# hmc_power.net
KiCad netlist of a schematic drawn in EAGLE
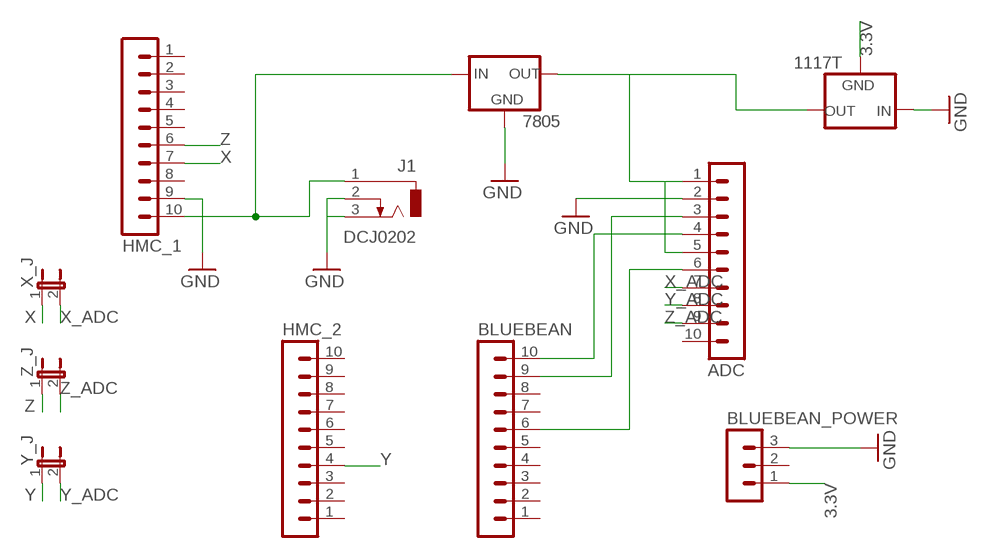
[diagram p0: schematic, sheet 1]

(export (version "E")
  (design (tool "Eeschema 10.0.6"))
  (components
    (comp (ref "1117T")
      (value "78XXL")
      (footprint "eagle-import:78XXL")
      (libsource (lib "eagle-import") (part "78XXL"))
    )
    (comp (ref "7805")
      (value "78XXL")
      (footprint "eagle-import:78XXL")
      (libsource (lib "eagle-import") (part "78XXL"))
    )
    (comp (ref "ADC")
      (value "MA10-1")
      (footprint "eagle-import:MA10-1")
      (libsource (lib "eagle-import") (part "MA10-1"))
    )
    (comp (ref "BLUEBEAN")
      (value "MA10-1")
      (footprint "eagle-import:MA10-1")
      (libsource (lib "eagle-import") (part "MA10-1"))
    )
    (comp (ref "BLUEBEAN_POWER")
      (value "MA03-1")
      (footprint "eagle-import:MA03-1")
      (libsource (lib "eagle-import") (part "MA03-1"))
    )
    (comp (ref "HMC_1")
      (value "MA10-1")
      (footprint "eagle-import:MA10-1")
      (libsource (lib "eagle-import") (part "MA10-1"))
    )
    (comp (ref "HMC_2")
      (value "MA10-1")
      (footprint "eagle-import:MA10-1")
      (libsource (lib "eagle-import") (part "MA10-1"))
    )
    (comp (ref "J1")
      (value "DCJ0202")
      (footprint "eagle-import:DCJ0202")
      (libsource (lib "eagle-import") (part "DCJ0202"))
    )
    (comp (ref "X_J")
      (value "JP1E")
      (footprint "eagle-import:JP1")
      (libsource (lib "eagle-import") (part "JP1E"))
    )
    (comp (ref "Y_J")
      (value "JP1E")
      (footprint "eagle-import:JP1")
      (libsource (lib "eagle-import") (part "JP1E"))
    )
    (comp (ref "Z_J")
      (value "JP1E")
      (footprint "eagle-import:JP1")
      (libsource (lib "eagle-import") (part "JP1E"))
    )
  )
  (nets
    (net (code "1") (name "/3.3V") (class "Default")
      (node (ref "1117T") (pin "GND") (pinfunction "GND_GND") (pintype "input"))
      (node (ref "BLUEBEAN_POWER") (pin "1") (pinfunction "1_1") (pintype "passive"))
    )
    (net (code "2") (name "/X") (class "Default")
      (node (ref "HMC_1") (pin "7") (pinfunction "7_7") (pintype "passive"))
      (node (ref "X_J") (pin "1") (pinfunction "1_1") (pintype "passive"))
    )
    (net (code "3") (name "/X_ADC") (class "Default")
      (node (ref "ADC") (pin "7") (pinfunction "7_7") (pintype "passive"))
      (node (ref "X_J") (pin "2") (pinfunction "2_2") (pintype "passive"))
    )
    (net (code "4") (name "/Y") (class "Default")
      (node (ref "HMC_2") (pin "4") (pinfunction "4_4") (pintype "passive"))
      (node (ref "Y_J") (pin "1") (pinfunction "1_1") (pintype "passive"))
    )
    (net (code "5") (name "/Y_ADC") (class "Default")
      (node (ref "ADC") (pin "8") (pinfunction "8_8") (pintype "passive"))
      (node (ref "Y_J") (pin "2") (pinfunction "2_2") (pintype "passive"))
    )
    (net (code "6") (name "/Z") (class "Default")
      (node (ref "HMC_1") (pin "6") (pinfunction "6_6") (pintype "passive"))
      (node (ref "Z_J") (pin "1") (pinfunction "1_1") (pintype "passive"))
    )
    (net (code "7") (name "/Z_ADC") (class "Default")
      (node (ref "ADC") (pin "9") (pinfunction "9_9") (pintype "passive"))
      (node (ref "Z_J") (pin "2") (pinfunction "2_2") (pintype "passive"))
    )
    (net (code "8") (name "GND") (class "Default")
      (node (ref "1117T") (pin "IN") (pinfunction "IN_IN") (pintype "input"))
      (node (ref "7805") (pin "GND") (pinfunction "GND_GND") (pintype "input"))
      (node (ref "ADC") (pin "2") (pinfunction "2_2") (pintype "passive"))
      (node (ref "BLUEBEAN_POWER") (pin "3") (pinfunction "3_3") (pintype "passive"))
      (node (ref "HMC_1") (pin "9") (pinfunction "9_9") (pintype "passive"))
      (node (ref "J1") (pin "2") (pinfunction "2_2") (pintype "passive"))
      (node (ref "J1") (pin "3") (pinfunction "3_3") (pintype "passive"))
    )
    (net (code "9") (name "Net-(1117T-PadOUT)") (class "Default")
      (node (ref "1117T") (pin "OUT") (pinfunction "OUT_OUT") (pintype "passive"))
      (node (ref "7805") (pin "OUT") (pinfunction "OUT_OUT") (pintype "passive"))
      (node (ref "ADC") (pin "1") (pinfunction "1_1") (pintype "passive"))
      (node (ref "ADC") (pin "5") (pinfunction "5_5") (pintype "passive"))
    )
    (net (code "10") (name "Net-(7805-PadIN)") (class "Default")
      (node (ref "7805") (pin "IN") (pinfunction "IN_IN") (pintype "input"))
      (node (ref "HMC_1") (pin "10") (pinfunction "10_10") (pintype "passive"))
      (node (ref "J1") (pin "1") (pinfunction "1_1") (pintype "passive"))
    )
    (net (code "11") (name "Net-(ADC-Pad3)") (class "Default")
      (node (ref "ADC") (pin "3") (pinfunction "3_3") (pintype "passive"))
      (node (ref "BLUEBEAN") (pin "9") (pinfunction "9_9") (pintype "passive"))
    )
    (net (code "12") (name "Net-(ADC-Pad4)") (class "Default")
      (node (ref "ADC") (pin "4") (pinfunction "4_4") (pintype "passive"))
      (node (ref "BLUEBEAN") (pin "10") (pinfunction "10_10") (pintype "passive"))
    )
    (net (code "13") (name "Net-(ADC-Pad6)") (class "Default")
      (node (ref "ADC") (pin "6") (pinfunction "6_6") (pintype "passive"))
      (node (ref "BLUEBEAN") (pin "6") (pinfunction "6_6") (pintype "passive"))
    )
    (net (code "14") (name "unconnected-(ADC-Pad10)") (class "Default")
      (node (ref "ADC") (pin "10") (pinfunction "10_10") (pintype "passive"))
    )
    (net (code "15") (name "unconnected-(BLUEBEAN-Pad1)") (class "Default")
      (node (ref "BLUEBEAN") (pin "1") (pinfunction "1_1") (pintype "passive"))
    )
    (net (code "16") (name "unconnected-(BLUEBEAN-Pad2)") (class "Default")
      (node (ref "BLUEBEAN") (pin "2") (pinfunction "2_2") (pintype "passive"))
    )
    (net (code "17") (name "unconnected-(BLUEBEAN-Pad3)") (class "Default")
      (node (ref "BLUEBEAN") (pin "3") (pinfunction "3_3") (pintype "passive"))
    )
    (net (code "18") (name "unconnected-(BLUEBEAN-Pad4)") (class "Default")
      (node (ref "BLUEBEAN") (pin "4") (pinfunction "4_4") (pintype "passive"))
    )
    (net (code "19") (name "unconnected-(BLUEBEAN-Pad5)") (class "Default")
      (node (ref "BLUEBEAN") (pin "5") (pinfunction "5_5") (pintype "passive"))
    )
    (net (code "20") (name "unconnected-(BLUEBEAN-Pad7)") (class "Default")
      (node (ref "BLUEBEAN") (pin "7") (pinfunction "7_7") (pintype "passive"))
    )
    (net (code "21") (name "unconnected-(BLUEBEAN-Pad8)") (class "Default")
      (node (ref "BLUEBEAN") (pin "8") (pinfunction "8_8") (pintype "passive"))
    )
    (net (code "22") (name "unconnected-(BLUEBEAN_POWER-Pad2)") (class "Default")
      (node (ref "BLUEBEAN_POWER") (pin "2") (pinfunction "2_2") (pintype "passive"))
    )
    (net (code "23") (name "unconnected-(HMC_1-Pad1)") (class "Default")
      (node (ref "HMC_1") (pin "1") (pinfunction "1_1") (pintype "passive"))
    )
    (net (code "24") (name "unconnected-(HMC_1-Pad2)") (class "Default")
      (node (ref "HMC_1") (pin "2") (pinfunction "2_2") (pintype "passive"))
    )
    (net (code "25") (name "unconnected-(HMC_1-Pad3)") (class "Default")
      (node (ref "HMC_1") (pin "3") (pinfunction "3_3") (pintype "passive"))
    )
    (net (code "26") (name "unconnected-(HMC_1-Pad4)") (class "Default")
      (node (ref "HMC_1") (pin "4") (pinfunction "4_4") (pintype "passive"))
    )
    (net (code "27") (name "unconnected-(HMC_1-Pad5)") (class "Default")
      (node (ref "HMC_1") (pin "5") (pinfunction "5_5") (pintype "passive"))
    )
    (net (code "28") (name "unconnected-(HMC_1-Pad8)") (class "Default")
      (node (ref "HMC_1") (pin "8") (pinfunction "8_8") (pintype "passive"))
    )
    (net (code "29") (name "unconnected-(HMC_2-Pad1)") (class "Default")
      (node (ref "HMC_2") (pin "1") (pinfunction "1_1") (pintype "passive"))
    )
    (net (code "30") (name "unconnected-(HMC_2-Pad2)") (class "Default")
      (node (ref "HMC_2") (pin "2") (pinfunction "2_2") (pintype "passive"))
    )
    (net (code "31") (name "unconnected-(HMC_2-Pad3)") (class "Default")
      (node (ref "HMC_2") (pin "3") (pinfunction "3_3") (pintype "passive"))
    )
    (net (code "32") (name "unconnected-(HMC_2-Pad5)") (class "Default")
      (node (ref "HMC_2") (pin "5") (pinfunction "5_5") (pintype "passive"))
    )
    (net (code "33") (name "unconnected-(HMC_2-Pad6)") (class "Default")
      (node (ref "HMC_2") (pin "6") (pinfunction "6_6") (pintype "passive"))
    )
    (net (code "34") (name "unconnected-(HMC_2-Pad7)") (class "Default")
      (node (ref "HMC_2") (pin "7") (pinfunction "7_7") (pintype "passive"))
    )
    (net (code "35") (name "unconnected-(HMC_2-Pad8)") (class "Default")
      (node (ref "HMC_2") (pin "8") (pinfunction "8_8") (pintype "passive"))
    )
    (net (code "36") (name "unconnected-(HMC_2-Pad9)") (class "Default")
      (node (ref "HMC_2") (pin "9") (pinfunction "9_9") (pintype "passive"))
    )
    (net (code "37") (name "unconnected-(HMC_2-Pad10)") (class "Default")
      (node (ref "HMC_2") (pin "10") (pinfunction "10_10") (pintype "passive"))
    )
  )
)
